# Bond-C3-Mini-VL-ALS.net
KiCad netlist of a schematic drawn in EAGLE
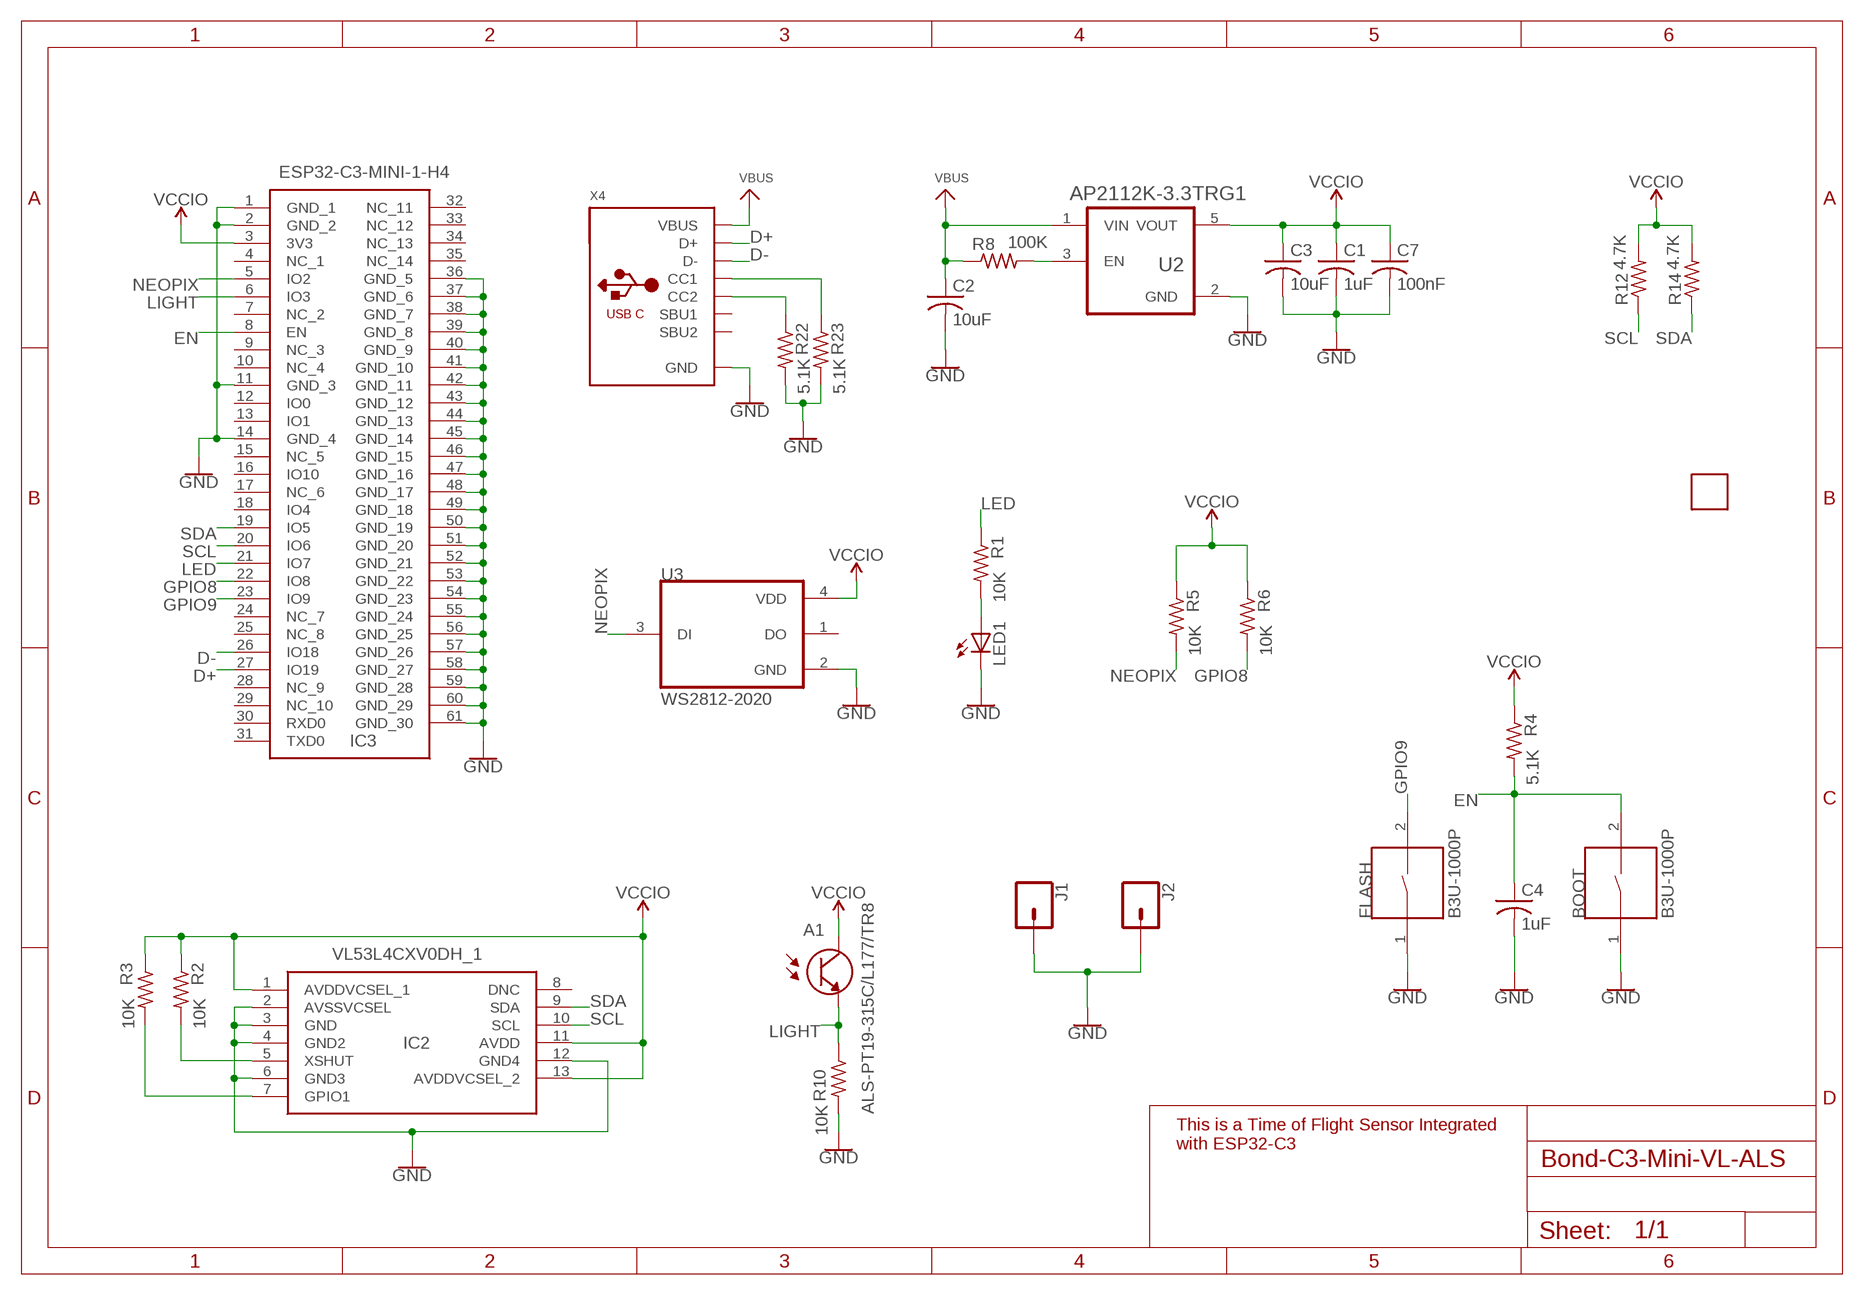
[diagram p0: schematic, sheet 1]

(export (version "E")
  (design (tool "Eeschema 10.0.6"))
  (components
    (comp (ref "A1")
      (value "ALS-PT19-315C/L177/TR8")
      (footprint "eagle-import:XDCR_ALS-PT19-315C_L177_TR8")
      (fields (field (name "MF") "Everlight"))
      (libsource (lib "eagle-import") (part "ALS-PT19-315C/L177/TR8"))
    )
    (comp (ref "BOOT")
      (value "B3U-1000P")
      (footprint "eagle-import:SW_B3U-1000P")
      (fields (field (name "MF") "Omron"))
      (libsource (lib "eagle-import") (part "B3U-1000P"))
    )
    (comp (ref "C1")
      (value "1uF")
      (footprint "eagle-import:C0402")
      (libsource (lib "eagle-import") (part "C-USC0402"))
    )
    (comp (ref "C2")
      (value "10uF")
      (footprint "eagle-import:C0402")
      (libsource (lib "eagle-import") (part "C-USC0402"))
    )
    (comp (ref "C3")
      (value "10uF")
      (footprint "eagle-import:C0402")
      (libsource (lib "eagle-import") (part "C-USC0402"))
    )
    (comp (ref "C4")
      (value "1uF")
      (footprint "eagle-import:C0402")
      (libsource (lib "eagle-import") (part "C-USC0402"))
    )
    (comp (ref "C7")
      (value "100nF")
      (footprint "eagle-import:C0402")
      (libsource (lib "eagle-import") (part "C-USC0402"))
    )
    (comp (ref "FLASH")
      (value "B3U-1000P")
      (footprint "eagle-import:SW_B3U-1000P")
      (fields (field (name "MF") "Omron"))
      (libsource (lib "eagle-import") (part "B3U-1000P"))
    )
    (comp (ref "IC2")
      (value "VL53L4CXV0DH_1")
      (footprint "eagle-import:VL53L4CXV0DH1")
      (fields
        (field (name "MANUFACTURER_PART_NUMBER") "VL53L4CXV0DH/1")
        (field (name "MOUSER_PART_NUMBER") "511-VL53L4CXV0DH/1")
      )
      (libsource (lib "eagle-import") (part "VL53L4CXV0DH_1"))
    )
    (comp (ref "IC3")
      (value "ESP32-C3-MINI-1-H4")
      (footprint "eagle-import:ESP32C3MINI1H4")
      (fields (field (name "MOUSER_PART_NUMBER") "356-ESP32-C3-MINI1H4"))
      (libsource (lib "eagle-import") (part "ESP32-C3-MINI-1-H4"))
    )
    (comp (ref "J1")
      (value "CONN_01PTH_2MM")
      (footprint "eagle-import:1X01_2MM")
      (libsource (lib "eagle-import") (part "CONN_01PTH_2MM"))
    )
    (comp (ref "J2")
      (value "CONN_01PTH_2MM")
      (footprint "eagle-import:1X01_2MM")
      (libsource (lib "eagle-import") (part "CONN_01PTH_2MM"))
    )
    (comp (ref "LED1")
      (value "LEDCHIP-LED0603")
      (footprint "eagle-import:CHIP-LED0603")
      (libsource (lib "eagle-import") (part "LEDCHIP-LED0603"))
    )
    (comp (ref "R1")
      (value "10K")
      (footprint "eagle-import:R0402")
      (libsource (lib "eagle-import") (part "R-US_R0402"))
    )
    (comp (ref "R2")
      (value "10K")
      (footprint "eagle-import:R0402")
      (libsource (lib "eagle-import") (part "R-US_R0402"))
    )
    (comp (ref "R3")
      (value "10K")
      (footprint "eagle-import:R0402")
      (libsource (lib "eagle-import") (part "R-US_R0402"))
    )
    (comp (ref "R4")
      (value "5.1K")
      (footprint "eagle-import:R0402")
      (libsource (lib "eagle-import") (part "R-US_R0402"))
    )
    (comp (ref "R5")
      (value "10K")
      (footprint "eagle-import:R0402")
      (libsource (lib "eagle-import") (part "R-US_R0402"))
    )
    (comp (ref "R6")
      (value "10K")
      (footprint "eagle-import:R0402")
      (libsource (lib "eagle-import") (part "R-US_R0402"))
    )
    (comp (ref "R8")
      (value "100K")
      (footprint "eagle-import:R0402")
      (libsource (lib "eagle-import") (part "R-US_R0402"))
    )
    (comp (ref "R10")
      (value "10K")
      (footprint "eagle-import:R0402")
      (libsource (lib "eagle-import") (part "R-US_R0402"))
    )
    (comp (ref "R12")
      (value "4.7K")
      (footprint "eagle-import:R0402")
      (libsource (lib "eagle-import") (part "R-US_R0402"))
    )
    (comp (ref "R14")
      (value "4.7K")
      (footprint "eagle-import:R0402")
      (libsource (lib "eagle-import") (part "R-US_R0402"))
    )
    (comp (ref "R22")
      (value "5.1K")
      (footprint "eagle-import:R0402")
      (libsource (lib "eagle-import") (part "R-US_R0402"))
    )
    (comp (ref "R23")
      (value "5.1K")
      (footprint "eagle-import:R0402")
      (libsource (lib "eagle-import") (part "R-US_R0402"))
    )
    (comp (ref "U$1")
      (value "SMARTT_SMALL")
      (footprint "eagle-import:SMARTT_SMALL")
      (libsource (lib "eagle-import") (part "SMARTT_SMALL"))
    )
    (comp (ref "U2")
      (value "AP2112K-3.3TRG1")
      (footprint "eagle-import:SOT95P285X140-5N")
      (fields (field (name "MF") "Diodes Inc."))
      (libsource (lib "eagle-import") (part "AP2112K-3.3TRG1"))
    )
    (comp (ref "U3")
      (value "WS2812-2020")
      (footprint "eagle-import:LED_WS2812-2020")
      (fields (field (name "MF") "Worldsemi"))
      (libsource (lib "eagle-import") (part "WS2812-2020"))
    )
    (comp (ref "X4")
      (value "MICROBUILDER_USB_C")
      (footprint "eagle-import:MICROBUILDER_USB_C_CUSB31-CFM2AX-01-X")
      (libsource (lib "eagle-import") (part "MICROBUILDER_USB_C"))
    )
  )
  (nets
    (net (code "1") (name "/D+") (class "Default")
      (node (ref "IC3") (pin "27") (pinfunction "IO19_27") (pintype "bidirectional"))
      (node (ref "X4") (pin "A6") (pinfunction "D+_A6") (pintype "bidirectional"))
      (node (ref "X4") (pin "B6") (pinfunction "D+_B6") (pintype "bidirectional"))
    )
    (net (code "2") (name "/D-") (class "Default")
      (node (ref "IC3") (pin "26") (pinfunction "IO18_26") (pintype "bidirectional"))
      (node (ref "X4") (pin "A7") (pinfunction "D-_A7") (pintype "bidirectional"))
      (node (ref "X4") (pin "B7") (pinfunction "D-_B7") (pintype "bidirectional"))
    )
    (net (code "3") (name "/EN") (class "Default")
      (node (ref "BOOT") (pin "2") (pinfunction "2_2") (pintype "passive"))
      (node (ref "C4") (pin "1") (pinfunction "1_1") (pintype "passive"))
      (node (ref "IC3") (pin "8") (pinfunction "EN_8") (pintype "bidirectional"))
      (node (ref "R4") (pin "2") (pinfunction "2_2") (pintype "passive"))
    )
    (net (code "4") (name "/GPIO8") (class "Default")
      (node (ref "IC3") (pin "22") (pinfunction "IO8_22") (pintype "bidirectional"))
      (node (ref "R6") (pin "2") (pinfunction "2_2") (pintype "passive"))
    )
    (net (code "5") (name "/GPIO9") (class "Default")
      (node (ref "FLASH") (pin "2") (pinfunction "2_2") (pintype "passive"))
      (node (ref "IC3") (pin "23") (pinfunction "IO9_23") (pintype "bidirectional"))
    )
    (net (code "6") (name "/LED") (class "Default")
      (node (ref "IC3") (pin "21") (pinfunction "IO7_21") (pintype "bidirectional"))
      (node (ref "R1") (pin "1") (pinfunction "1_1") (pintype "passive"))
    )
    (net (code "7") (name "/LIGHT") (class "Default")
      (node (ref "A1") (pin "2") (pinfunction "E_2") (pintype "passive"))
      (node (ref "IC3") (pin "6") (pinfunction "IO3_6") (pintype "bidirectional"))
      (node (ref "R10") (pin "1") (pinfunction "1_1") (pintype "passive"))
    )
    (net (code "8") (name "/NEOPIX") (class "Default")
      (node (ref "IC3") (pin "5") (pinfunction "IO2_5") (pintype "bidirectional"))
      (node (ref "R5") (pin "2") (pinfunction "2_2") (pintype "passive"))
      (node (ref "U3") (pin "3") (pinfunction "DI_3") (pintype "input"))
    )
    (net (code "9") (name "/SCL") (class "Default")
      (node (ref "IC2") (pin "10") (pinfunction "SCL_10") (pintype "bidirectional"))
      (node (ref "IC3") (pin "20") (pinfunction "IO6_20") (pintype "bidirectional"))
      (node (ref "R12") (pin "1") (pinfunction "1_1") (pintype "passive"))
    )
    (net (code "10") (name "/SDA") (class "Default")
      (node (ref "IC2") (pin "9") (pinfunction "SDA_9") (pintype "bidirectional"))
      (node (ref "IC3") (pin "19") (pinfunction "IO5_19") (pintype "bidirectional"))
      (node (ref "R14") (pin "1") (pinfunction "1_1") (pintype "passive"))
    )
    (net (code "11") (name "GND") (class "Default")
      (node (ref "BOOT") (pin "1") (pinfunction "1_1") (pintype "passive"))
      (node (ref "C1") (pin "2") (pinfunction "2_2") (pintype "passive"))
      (node (ref "C2") (pin "2") (pinfunction "2_2") (pintype "passive"))
      (node (ref "C3") (pin "2") (pinfunction "2_2") (pintype "passive"))
      (node (ref "C4") (pin "2") (pinfunction "2_2") (pintype "passive"))
      (node (ref "C7") (pin "2") (pinfunction "2_2") (pintype "passive"))
      (node (ref "FLASH") (pin "1") (pinfunction "1_1") (pintype "passive"))
      (node (ref "IC2") (pin "12") (pinfunction "GND4_12") (pintype "bidirectional"))
      (node (ref "IC2") (pin "2") (pinfunction "AVSSVCSEL_2") (pintype "bidirectional"))
      (node (ref "IC2") (pin "3") (pinfunction "GND_3") (pintype "bidirectional"))
      (node (ref "IC2") (pin "4") (pinfunction "GND2_4") (pintype "bidirectional"))
      (node (ref "IC2") (pin "6") (pinfunction "GND3_6") (pintype "bidirectional"))
      (node (ref "IC3") (pin "1") (pinfunction "GND_1_1") (pintype "bidirectional"))
      (node (ref "IC3") (pin "11") (pinfunction "GND_3_11") (pintype "bidirectional"))
      (node (ref "IC3") (pin "14") (pinfunction "GND_4_14") (pintype "bidirectional"))
      (node (ref "IC3") (pin "2") (pinfunction "GND_2_2") (pintype "bidirectional"))
      (node (ref "IC3") (pin "36") (pinfunction "GND_5_36") (pintype "bidirectional"))
      (node (ref "IC3") (pin "37") (pinfunction "GND_6_37") (pintype "bidirectional"))
      (node (ref "IC3") (pin "38") (pinfunction "GND_7_38") (pintype "bidirectional"))
      (node (ref "IC3") (pin "39") (pinfunction "GND_8_39") (pintype "bidirectional"))
      (node (ref "IC3") (pin "40") (pinfunction "GND_9_40") (pintype "bidirectional"))
      (node (ref "IC3") (pin "41") (pinfunction "GND_10_41") (pintype "bidirectional"))
      (node (ref "IC3") (pin "42") (pinfunction "GND_11_42") (pintype "bidirectional"))
      (node (ref "IC3") (pin "43") (pinfunction "GND_12_43") (pintype "bidirectional"))
      (node (ref "IC3") (pin "44") (pinfunction "GND_13_44") (pintype "bidirectional"))
      (node (ref "IC3") (pin "45") (pinfunction "GND_14_45") (pintype "bidirectional"))
      (node (ref "IC3") (pin "46") (pinfunction "GND_15_46") (pintype "bidirectional"))
      (node (ref "IC3") (pin "47") (pinfunction "GND_16_47") (pintype "bidirectional"))
      (node (ref "IC3") (pin "48") (pinfunction "GND_17_48") (pintype "bidirectional"))
      (node (ref "IC3") (pin "49") (pinfunction "GND_18_49") (pintype "bidirectional"))
      (node (ref "IC3") (pin "50") (pinfunction "GND_19_50") (pintype "bidirectional"))
      (node (ref "IC3") (pin "51") (pinfunction "GND_20_51") (pintype "bidirectional"))
      (node (ref "IC3") (pin "52") (pinfunction "GND_21_52") (pintype "bidirectional"))
      (node (ref "IC3") (pin "53") (pinfunction "GND_22_53") (pintype "bidirectional"))
      (node (ref "IC3") (pin "54") (pinfunction "GND_23_54") (pintype "bidirectional"))
      (node (ref "IC3") (pin "55") (pinfunction "GND_24_55") (pintype "bidirectional"))
      (node (ref "IC3") (pin "56") (pinfunction "GND_25_56") (pintype "bidirectional"))
      (node (ref "IC3") (pin "57") (pinfunction "GND_26_57") (pintype "bidirectional"))
      (node (ref "IC3") (pin "58") (pinfunction "GND_27_58") (pintype "bidirectional"))
      (node (ref "IC3") (pin "59") (pinfunction "GND_28_59") (pintype "bidirectional"))
      (node (ref "IC3") (pin "60") (pinfunction "GND_29_60") (pintype "bidirectional"))
      (node (ref "IC3") (pin "61") (pinfunction "GND_30_61") (pintype "bidirectional"))
      (node (ref "J1") (pin "1") (pinfunction "1_1") (pintype "passive"))
      (node (ref "J2") (pin "1") (pinfunction "1_1") (pintype "passive"))
      (node (ref "LED1") (pin "C") (pinfunction "C_C") (pintype "passive"))
      (node (ref "R10") (pin "2") (pinfunction "2_2") (pintype "passive"))
      (node (ref "R22") (pin "2") (pinfunction "2_2") (pintype "passive"))
      (node (ref "R23") (pin "2") (pinfunction "2_2") (pintype "passive"))
      (node (ref "U2") (pin "2") (pinfunction "GND_2") (pintype "power_in"))
      (node (ref "U3") (pin "2") (pinfunction "GND_2") (pintype "power_in"))
      (node (ref "X4") (pin "A1B12") (pinfunction "GND_A1B12") (pintype "power_in"))
      (node (ref "X4") (pin "B1A12") (pinfunction "GND_B1A12") (pintype "power_in"))
    )
    (net (code "12") (name "Net-(IC2-GPIO1)") (class "Default")
      (node (ref "IC2") (pin "7") (pinfunction "GPIO1_7") (pintype "bidirectional"))
      (node (ref "R3") (pin "2") (pinfunction "2_2") (pintype "passive"))
    )
    (net (code "13") (name "Net-(IC2-XSHUT)") (class "Default")
      (node (ref "IC2") (pin "5") (pinfunction "XSHUT_5") (pintype "bidirectional"))
      (node (ref "R2") (pin "2") (pinfunction "2_2") (pintype "passive"))
    )
    (net (code "14") (name "Net-(LED1-PadA)") (class "Default")
      (node (ref "LED1") (pin "A") (pinfunction "A_A") (pintype "passive"))
      (node (ref "R1") (pin "2") (pinfunction "2_2") (pintype "passive"))
    )
    (net (code "15") (name "Net-(U2-EN)") (class "Default")
      (node (ref "R8") (pin "2") (pinfunction "2_2") (pintype "passive"))
      (node (ref "U2") (pin "3") (pinfunction "EN_3") (pintype "input"))
    )
    (net (code "16") (name "Net-(X4-CC1)") (class "Default")
      (node (ref "R23") (pin "1") (pinfunction "1_1") (pintype "passive"))
      (node (ref "X4") (pin "A5") (pinfunction "CC1_A5") (pintype "bidirectional"))
    )
    (net (code "17") (name "Net-(X4-CC2)") (class "Default")
      (node (ref "R22") (pin "1") (pinfunction "1_1") (pintype "passive"))
      (node (ref "X4") (pin "B5") (pinfunction "CC2_B5") (pintype "bidirectional"))
    )
    (net (code "18") (name "VBUS") (class "Default")
      (node (ref "C2") (pin "1") (pinfunction "1_1") (pintype "passive"))
      (node (ref "R8") (pin "1") (pinfunction "1_1") (pintype "passive"))
      (node (ref "U2") (pin "1") (pinfunction "VIN_1") (pintype "power_in"))
      (node (ref "X4") (pin "A4B9") (pinfunction "VBUS_A4B9") (pintype "power_in"))
      (node (ref "X4") (pin "B4A9") (pinfunction "VBUS_B4A9") (pintype "power_in"))
    )
    (net (code "19") (name "VCCIO") (class "Default")
      (node (ref "A1") (pin "1") (pinfunction "C_1") (pintype "passive"))
      (node (ref "C1") (pin "1") (pinfunction "1_1") (pintype "passive"))
      (node (ref "C3") (pin "1") (pinfunction "1_1") (pintype "passive"))
      (node (ref "C7") (pin "1") (pinfunction "1_1") (pintype "passive"))
      (node (ref "IC2") (pin "1") (pinfunction "AVDDVCSEL_1_1") (pintype "bidirectional"))
      (node (ref "IC2") (pin "11") (pinfunction "AVDD_11") (pintype "bidirectional"))
      (node (ref "IC2") (pin "13") (pinfunction "AVDDVCSEL_2_13") (pintype "bidirectional"))
      (node (ref "IC3") (pin "3") (pinfunction "3V3_3") (pintype "bidirectional"))
      (node (ref "R12") (pin "2") (pinfunction "2_2") (pintype "passive"))
      (node (ref "R14") (pin "2") (pinfunction "2_2") (pintype "passive"))
      (node (ref "R2") (pin "1") (pinfunction "1_1") (pintype "passive"))
      (node (ref "R3") (pin "1") (pinfunction "1_1") (pintype "passive"))
      (node (ref "R4") (pin "1") (pinfunction "1_1") (pintype "passive"))
      (node (ref "R5") (pin "1") (pinfunction "1_1") (pintype "passive"))
      (node (ref "R6") (pin "1") (pinfunction "1_1") (pintype "passive"))
      (node (ref "U2") (pin "5") (pinfunction "VOUT_5") (pintype "power_in"))
      (node (ref "U3") (pin "4") (pinfunction "VDD_4") (pintype "power_in"))
    )
    (net (code "20") (name "unconnected-(IC2-DNC-Pad8)") (class "Default")
      (node (ref "IC2") (pin "8") (pinfunction "DNC_8") (pintype "bidirectional"))
    )
    (net (code "21") (name "unconnected-(IC3-IO0-Pad12)") (class "Default")
      (node (ref "IC3") (pin "12") (pinfunction "IO0_12") (pintype "bidirectional"))
    )
    (net (code "22") (name "unconnected-(IC3-IO1-Pad13)") (class "Default")
      (node (ref "IC3") (pin "13") (pinfunction "IO1_13") (pintype "bidirectional"))
    )
    (net (code "23") (name "unconnected-(IC3-IO4-Pad18)") (class "Default")
      (node (ref "IC3") (pin "18") (pinfunction "IO4_18") (pintype "bidirectional"))
    )
    (net (code "24") (name "unconnected-(IC3-IO10-Pad16)") (class "Default")
      (node (ref "IC3") (pin "16") (pinfunction "IO10_16") (pintype "bidirectional"))
    )
    (net (code "25") (name "unconnected-(IC3-NC_1-Pad4)") (class "Default")
      (node (ref "IC3") (pin "4") (pinfunction "NC_1_4") (pintype "bidirectional"))
    )
    (net (code "26") (name "unconnected-(IC3-NC_2-Pad7)") (class "Default")
      (node (ref "IC3") (pin "7") (pinfunction "NC_2_7") (pintype "bidirectional"))
    )
    (net (code "27") (name "unconnected-(IC3-NC_3-Pad9)") (class "Default")
      (node (ref "IC3") (pin "9") (pinfunction "NC_3_9") (pintype "bidirectional"))
    )
    (net (code "28") (name "unconnected-(IC3-NC_4-Pad10)") (class "Default")
      (node (ref "IC3") (pin "10") (pinfunction "NC_4_10") (pintype "bidirectional"))
    )
    (net (code "29") (name "unconnected-(IC3-NC_5-Pad15)") (class "Default")
      (node (ref "IC3") (pin "15") (pinfunction "NC_5_15") (pintype "bidirectional"))
    )
    (net (code "30") (name "unconnected-(IC3-NC_6-Pad17)") (class "Default")
      (node (ref "IC3") (pin "17") (pinfunction "NC_6_17") (pintype "bidirectional"))
    )
    (net (code "31") (name "unconnected-(IC3-NC_7-Pad24)") (class "Default")
      (node (ref "IC3") (pin "24") (pinfunction "NC_7_24") (pintype "bidirectional"))
    )
    (net (code "32") (name "unconnected-(IC3-NC_8-Pad25)") (class "Default")
      (node (ref "IC3") (pin "25") (pinfunction "NC_8_25") (pintype "bidirectional"))
    )
    (net (code "33") (name "unconnected-(IC3-NC_9-Pad28)") (class "Default")
      (node (ref "IC3") (pin "28") (pinfunction "NC_9_28") (pintype "bidirectional"))
    )
    (net (code "34") (name "unconnected-(IC3-NC_10-Pad29)") (class "Default")
      (node (ref "IC3") (pin "29") (pinfunction "NC_10_29") (pintype "bidirectional"))
    )
    (net (code "35") (name "unconnected-(IC3-NC_11-Pad32)") (class "Default")
      (node (ref "IC3") (pin "32") (pinfunction "NC_11_32") (pintype "bidirectional"))
    )
    (net (code "36") (name "unconnected-(IC3-NC_12-Pad33)") (class "Default")
      (node (ref "IC3") (pin "33") (pinfunction "NC_12_33") (pintype "bidirectional"))
    )
    (net (code "37") (name "unconnected-(IC3-NC_13-Pad34)") (class "Default")
      (node (ref "IC3") (pin "34") (pinfunction "NC_13_34") (pintype "bidirectional"))
    )
    (net (code "38") (name "unconnected-(IC3-NC_14-Pad35)") (class "Default")
      (node (ref "IC3") (pin "35") (pinfunction "NC_14_35") (pintype "bidirectional"))
    )
    (net (code "39") (name "unconnected-(IC3-RXD0-Pad30)") (class "Default")
      (node (ref "IC3") (pin "30") (pinfunction "RXD0_30") (pintype "bidirectional"))
    )
    (net (code "40") (name "unconnected-(IC3-TXD0-Pad31)") (class "Default")
      (node (ref "IC3") (pin "31") (pinfunction "TXD0_31") (pintype "bidirectional"))
    )
    (net (code "41") (name "unconnected-(U3-DO-Pad1)") (class "Default")
      (node (ref "U3") (pin "1") (pinfunction "DO_1") (pintype "output"))
    )
    (net (code "42") (name "unconnected-(X4-SBU1-PadA8)") (class "Default")
      (node (ref "X4") (pin "A8") (pinfunction "SBU1_A8") (pintype "bidirectional"))
    )
    (net (code "43") (name "unconnected-(X4-SBU2-PadB8)") (class "Default")
      (node (ref "X4") (pin "B8") (pinfunction "SBU2_B8") (pintype "bidirectional"))
    )
  )
)
